# canmotor.net
KiCad netlist of a schematic drawn in EAGLE
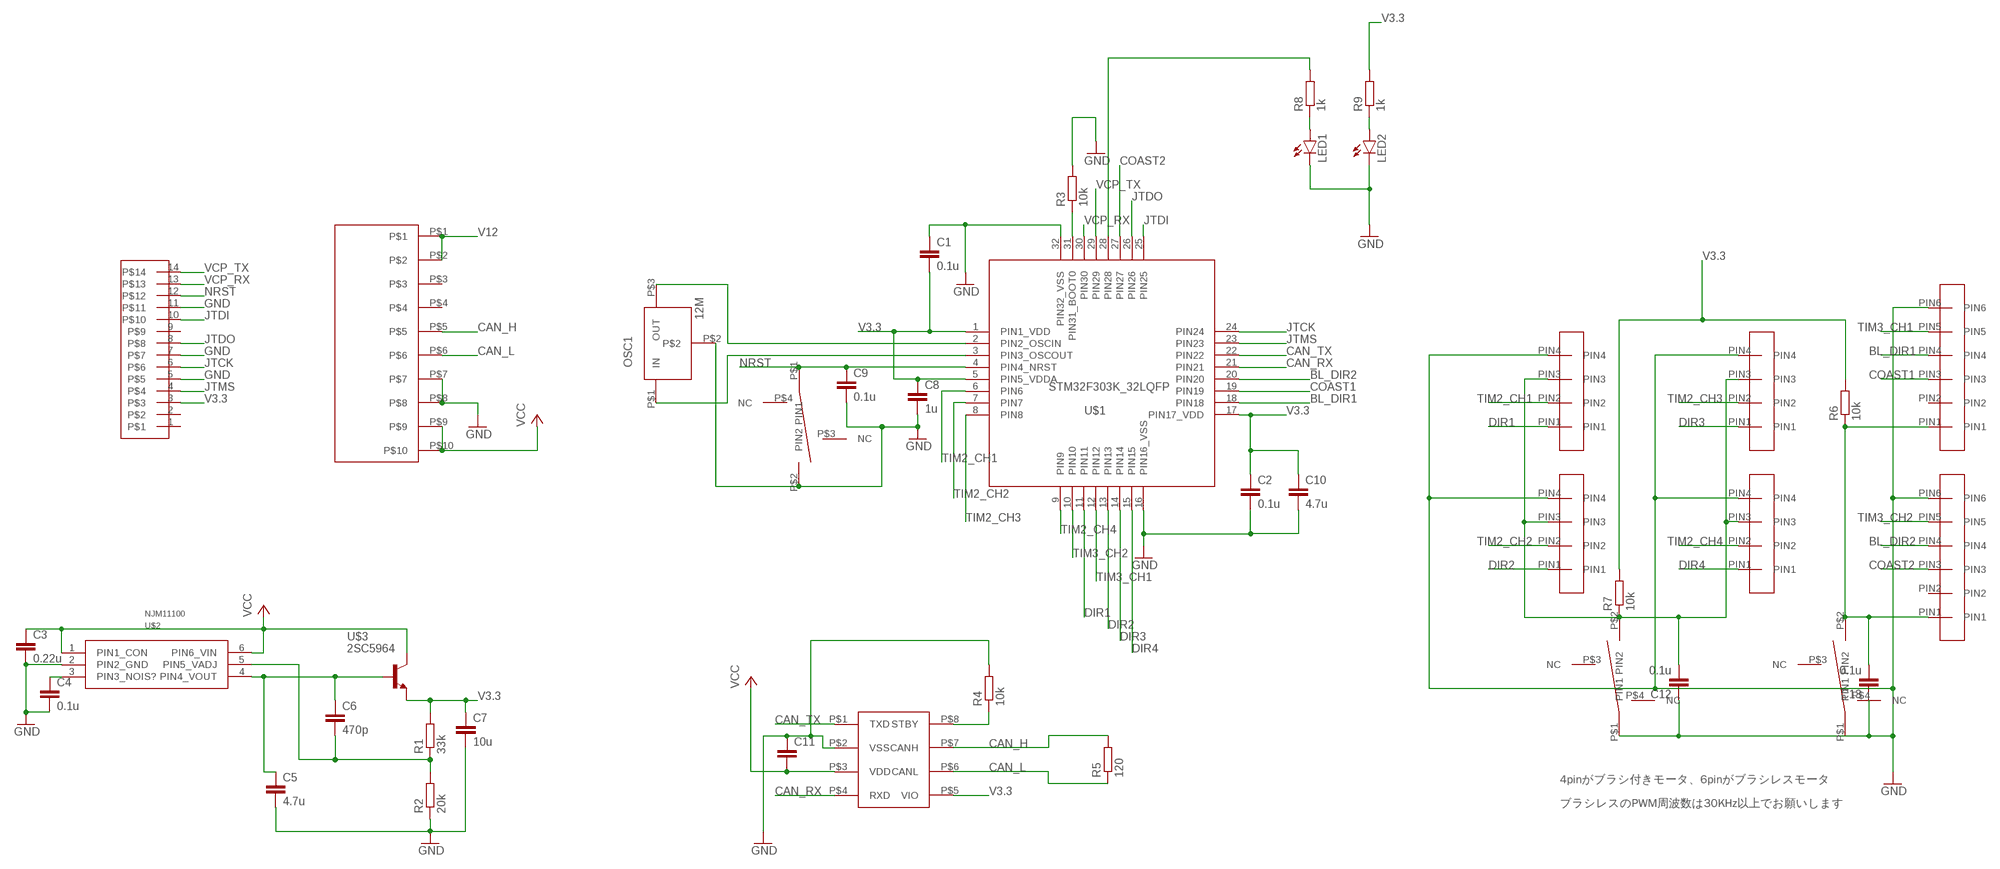
[diagram p0: schematic, sheet 1]

(export (version "E")
  (design (tool "Eeschema 10.0.6"))
  (components
    (comp (ref "BOX10P-L2")
      (value "BOX10PBOX10P-L")
      (footprint "eagle-import:BOX10P-L")
      (libsource (lib "eagle-import") (part "BOX10PBOX10P-L"))
    )
    (comp (ref "C1")
      (value "0.1u")
      (footprint "eagle-import:C1608")
      (libsource (lib "eagle-import") (part "C-EUC1608"))
    )
    (comp (ref "C2")
      (value "0.1u")
      (footprint "eagle-import:C1608")
      (libsource (lib "eagle-import") (part "C-EUC1608"))
    )
    (comp (ref "C3")
      (value "0.22u")
      (footprint "eagle-import:C2012")
      (libsource (lib "eagle-import") (part "C-EUC2012"))
    )
    (comp (ref "C4")
      (value "0.1u")
      (footprint "eagle-import:C1608")
      (libsource (lib "eagle-import") (part "C-EUC1608"))
    )
    (comp (ref "C5")
      (value "4.7u")
      (footprint "eagle-import:C2012")
      (libsource (lib "eagle-import") (part "C-EUC2012"))
    )
    (comp (ref "C6")
      (value "470p")
      (footprint "eagle-import:C1608")
      (libsource (lib "eagle-import") (part "C-EUC1608"))
    )
    (comp (ref "C7")
      (value "10u")
      (footprint "eagle-import:C2012")
      (libsource (lib "eagle-import") (part "C-EUC2012"))
    )
    (comp (ref "C8")
      (value "1u")
      (footprint "eagle-import:C1608")
      (libsource (lib "eagle-import") (part "C-EUC1608"))
    )
    (comp (ref "C9")
      (value "0.1u")
      (footprint "eagle-import:C1608")
      (libsource (lib "eagle-import") (part "C-EUC1608"))
    )
    (comp (ref "C10")
      (value "4.7u")
      (footprint "eagle-import:C2012")
      (libsource (lib "eagle-import") (part "C-EUC2012"))
    )
    (comp (ref "C11")
      (value "C-EUC1608")
      (footprint "eagle-import:C1608")
      (libsource (lib "eagle-import") (part "C-EUC1608"))
    )
    (comp (ref "C12")
      (value "0.1u")
      (footprint "eagle-import:C1608")
      (libsource (lib "eagle-import") (part "C-EUC1608"))
    )
    (comp (ref "C13")
      (value "0.1u")
      (footprint "eagle-import:C1608")
      (libsource (lib "eagle-import") (part "C-EUC1608"))
    )
    (comp (ref "LED1")
      (value "1608LED")
      (footprint "eagle-import:1608")
      (libsource (lib "eagle-import") (part "1608LED"))
    )
    (comp (ref "LED2")
      (value "1608LED")
      (footprint "eagle-import:1608")
      (libsource (lib "eagle-import") (part "1608LED"))
    )
    (comp (ref "OSC1")
      (value "12M")
      (footprint "eagle-import:CSTNE#")
      (libsource (lib "eagle-import") (part "CSTN#"))
    )
    (comp (ref "R1")
      (value "33k")
      (footprint "eagle-import:1608")
      (libsource (lib "eagle-import") (part "R_REG"))
    )
    (comp (ref "R2")
      (value "20k")
      (footprint "eagle-import:1608")
      (libsource (lib "eagle-import") (part "R_REG"))
    )
    (comp (ref "R3")
      (value "10k")
      (footprint "eagle-import:1608")
      (libsource (lib "eagle-import") (part "R_REG"))
    )
    (comp (ref "R4")
      (value "10k")
      (footprint "eagle-import:1608")
      (libsource (lib "eagle-import") (part "R_REG"))
    )
    (comp (ref "R5")
      (value "120")
      (footprint "eagle-import:1608")
      (libsource (lib "eagle-import") (part "R_REG"))
    )
    (comp (ref "R6")
      (value "10k")
      (footprint "eagle-import:1608")
      (libsource (lib "eagle-import") (part "R_REG"))
    )
    (comp (ref "R7")
      (value "10k")
      (footprint "eagle-import:1608")
      (libsource (lib "eagle-import") (part "R_REG"))
    )
    (comp (ref "R8")
      (value "1k")
      (footprint "eagle-import:1608")
      (libsource (lib "eagle-import") (part "R_REG"))
    )
    (comp (ref "R9")
      (value "1k")
      (footprint "eagle-import:1608")
      (libsource (lib "eagle-import") (part "R_REG"))
    )
    (comp (ref "U$1")
      (value "STM32F303K_32LQFP")
      (footprint "eagle-import:LQFP32-7X7")
      (libsource (lib "eagle-import") (part "STM32F303K_32LQFP"))
    )
    (comp (ref "U$2")
      (value "NJM11100")
      (footprint "eagle-import:SOT23-6")
      (libsource (lib "eagle-import") (part "NJM11100"))
    )
    (comp (ref "U$3")
      (value "2SC5964")
      (footprint "eagle-import:PCP")
      (libsource (lib "eagle-import") (part "2SC5964"))
    )
    (comp (ref "U$4")
      (value "TAKUTOSUITTI2")
      (footprint "eagle-import:TAKUTOSUITTI2")
      (libsource (lib "eagle-import") (part "TAKUTOSUITTI2"))
    )
    (comp (ref "U$5")
      (value "MCP2562MCP2561-SN")
      (footprint "eagle-import:SOIC8")
      (libsource (lib "eagle-import") (part "MCP2562MCP2561-SN"))
    )
    (comp (ref "U$6")
      (value "BOX14P")
      (footprint "eagle-import:CON_HEDA14P_1.27")
      (libsource (lib "eagle-import") (part "BOX14P"))
    )
    (comp (ref "U$7")
      (value "DF1B_L_6P")
      (footprint "eagle-import:DF1B_L_6P")
      (libsource (lib "eagle-import") (part "DF1B_L_6P"))
    )
    (comp (ref "U$8")
      (value "DF1B_L_4P")
      (footprint "eagle-import:DF1B_L_4P")
      (libsource (lib "eagle-import") (part "DF1B_L_4P"))
    )
    (comp (ref "U$9")
      (value "DF1B_L_4P")
      (footprint "eagle-import:DF1B_L_4P")
      (libsource (lib "eagle-import") (part "DF1B_L_4P"))
    )
    (comp (ref "U$10")
      (value "DF1B_L_4P")
      (footprint "eagle-import:DF1B_L_4P")
      (libsource (lib "eagle-import") (part "DF1B_L_4P"))
    )
    (comp (ref "U$11")
      (value "DF1B_L_4P")
      (footprint "eagle-import:DF1B_L_4P")
      (libsource (lib "eagle-import") (part "DF1B_L_4P"))
    )
    (comp (ref "U$12")
      (value "DF1B_L_6P")
      (footprint "eagle-import:DF1B_L_6P")
      (libsource (lib "eagle-import") (part "DF1B_L_6P"))
    )
    (comp (ref "U$13")
      (value "TAKUTOSUITTI2")
      (footprint "eagle-import:TAKUTOSUITTI2")
      (libsource (lib "eagle-import") (part "TAKUTOSUITTI2"))
    )
    (comp (ref "U$14")
      (value "TAKUTOSUITTI2")
      (footprint "eagle-import:TAKUTOSUITTI2")
      (libsource (lib "eagle-import") (part "TAKUTOSUITTI2"))
    )
  )
  (nets
    (net (code "1") (name "/BL_DIR1") (class "Default")
      (node (ref "U$1") (pin "18") (pinfunction "PIN18_18") (pintype "bidirectional"))
      (node (ref "U$7") (pin "PIN4") (pinfunction "PIN4_PIN4") (pintype "bidirectional"))
    )
    (net (code "2") (name "/BL_DIR2") (class "Default")
      (node (ref "U$1") (pin "20") (pinfunction "PIN20_20") (pintype "bidirectional"))
      (node (ref "U$12") (pin "PIN4") (pinfunction "PIN4_PIN4") (pintype "bidirectional"))
    )
    (net (code "3") (name "/CAN_H") (class "Default")
      (node (ref "BOX10P-L2") (pin "P$5") (pinfunction "P$5_P$5") (pintype "bidirectional"))
      (node (ref "R5") (pin "2") (pinfunction "2_2") (pintype "passive"))
      (node (ref "U$5") (pin "P$7") (pinfunction "CANH_P$7") (pintype "bidirectional"))
    )
    (net (code "4") (name "/CAN_L") (class "Default")
      (node (ref "BOX10P-L2") (pin "P$6") (pinfunction "P$6_P$6") (pintype "bidirectional"))
      (node (ref "R5") (pin "1") (pinfunction "1_1") (pintype "passive"))
      (node (ref "U$5") (pin "P$6") (pinfunction "CANL_P$6") (pintype "bidirectional"))
    )
    (net (code "5") (name "/CAN_RX") (class "Default")
      (node (ref "U$1") (pin "21") (pinfunction "PIN21_21") (pintype "bidirectional"))
      (node (ref "U$5") (pin "P$4") (pinfunction "RXD_P$4") (pintype "bidirectional"))
    )
    (net (code "6") (name "/CAN_TX") (class "Default")
      (node (ref "U$1") (pin "22") (pinfunction "PIN22_22") (pintype "bidirectional"))
      (node (ref "U$5") (pin "P$1") (pinfunction "TXD_P$1") (pintype "bidirectional"))
    )
    (net (code "7") (name "/COAST1") (class "Default")
      (node (ref "U$1") (pin "19") (pinfunction "PIN19_19") (pintype "bidirectional"))
      (node (ref "U$7") (pin "PIN3") (pinfunction "PIN3_PIN3") (pintype "bidirectional"))
    )
    (net (code "8") (name "/COAST2") (class "Default")
      (node (ref "U$1") (pin "27") (pinfunction "PIN27_27") (pintype "bidirectional"))
      (node (ref "U$12") (pin "PIN3") (pinfunction "PIN3_PIN3") (pintype "bidirectional"))
    )
    (net (code "9") (name "/DIR1") (class "Default")
      (node (ref "U$1") (pin "11") (pinfunction "PIN11_11") (pintype "bidirectional"))
      (node (ref "U$8") (pin "PIN1") (pinfunction "PIN1_PIN1") (pintype "bidirectional"))
    )
    (net (code "10") (name "/DIR2") (class "Default")
      (node (ref "U$1") (pin "13") (pinfunction "PIN13_13") (pintype "bidirectional"))
      (node (ref "U$9") (pin "PIN1") (pinfunction "PIN1_PIN1") (pintype "bidirectional"))
    )
    (net (code "11") (name "/DIR3") (class "Default")
      (node (ref "U$1") (pin "14") (pinfunction "PIN14_14") (pintype "bidirectional"))
      (node (ref "U$10") (pin "PIN1") (pinfunction "PIN1_PIN1") (pintype "bidirectional"))
    )
    (net (code "12") (name "/DIR4") (class "Default")
      (node (ref "U$1") (pin "15") (pinfunction "PIN15_15") (pintype "bidirectional"))
      (node (ref "U$11") (pin "PIN1") (pinfunction "PIN1_PIN1") (pintype "bidirectional"))
    )
    (net (code "13") (name "/JTCK") (class "Default")
      (node (ref "U$1") (pin "24") (pinfunction "PIN24_24") (pintype "bidirectional"))
      (node (ref "U$6") (pin "6") (pinfunction "P$6_6") (pintype "bidirectional"))
    )
    (net (code "14") (name "/JTDI") (class "Default")
      (node (ref "U$1") (pin "25") (pinfunction "PIN25_25") (pintype "bidirectional"))
      (node (ref "U$6") (pin "10") (pinfunction "P$10_10") (pintype "bidirectional"))
    )
    (net (code "15") (name "/JTDO") (class "Default")
      (node (ref "U$1") (pin "26") (pinfunction "PIN26_26") (pintype "bidirectional"))
      (node (ref "U$6") (pin "8") (pinfunction "P$8_8") (pintype "bidirectional"))
    )
    (net (code "16") (name "/JTMS") (class "Default")
      (node (ref "U$1") (pin "23") (pinfunction "PIN23_23") (pintype "bidirectional"))
      (node (ref "U$6") (pin "4") (pinfunction "P$4_4") (pintype "bidirectional"))
    )
    (net (code "17") (name "/NRST") (class "Default")
      (node (ref "C9") (pin "1") (pinfunction "1_1") (pintype "passive"))
      (node (ref "U$1") (pin "4") (pinfunction "PIN4_NRST_4") (pintype "bidirectional"))
      (node (ref "U$4") (pin "P$1") (pinfunction "PIN1_P$1") (pintype "bidirectional"))
      (node (ref "U$6") (pin "12") (pinfunction "P$12_12") (pintype "bidirectional"))
    )
    (net (code "18") (name "/TIM2_CH1") (class "Default")
      (node (ref "U$1") (pin "6") (pinfunction "PIN6_6") (pintype "bidirectional"))
      (node (ref "U$8") (pin "PIN2") (pinfunction "PIN2_PIN2") (pintype "bidirectional"))
    )
    (net (code "19") (name "/TIM2_CH2") (class "Default")
      (node (ref "U$1") (pin "7") (pinfunction "PIN7_7") (pintype "bidirectional"))
      (node (ref "U$9") (pin "PIN2") (pinfunction "PIN2_PIN2") (pintype "bidirectional"))
    )
    (net (code "20") (name "/TIM2_CH3") (class "Default")
      (node (ref "U$1") (pin "8") (pinfunction "PIN8_8") (pintype "bidirectional"))
      (node (ref "U$10") (pin "PIN2") (pinfunction "PIN2_PIN2") (pintype "bidirectional"))
    )
    (net (code "21") (name "/TIM2_CH4") (class "Default")
      (node (ref "U$1") (pin "9") (pinfunction "PIN9_9") (pintype "bidirectional"))
      (node (ref "U$11") (pin "PIN2") (pinfunction "PIN2_PIN2") (pintype "bidirectional"))
    )
    (net (code "22") (name "/TIM3_CH1") (class "Default")
      (node (ref "U$1") (pin "12") (pinfunction "PIN12_12") (pintype "bidirectional"))
      (node (ref "U$7") (pin "PIN5") (pinfunction "PIN5_PIN5") (pintype "bidirectional"))
    )
    (net (code "23") (name "/TIM3_CH2") (class "Default")
      (node (ref "U$1") (pin "10") (pinfunction "PIN10_10") (pintype "bidirectional"))
      (node (ref "U$12") (pin "PIN5") (pinfunction "PIN5_PIN5") (pintype "bidirectional"))
    )
    (net (code "24") (name "/V3.3") (class "Default")
      (node (ref "C1") (pin "2") (pinfunction "2_2") (pintype "passive"))
      (node (ref "C10") (pin "1") (pinfunction "1_1") (pintype "passive"))
      (node (ref "C2") (pin "1") (pinfunction "1_1") (pintype "passive"))
      (node (ref "C7") (pin "1") (pinfunction "1_1") (pintype "passive"))
      (node (ref "C8") (pin "1") (pinfunction "1_1") (pintype "passive"))
      (node (ref "R1") (pin "2") (pinfunction "2_2") (pintype "passive"))
      (node (ref "R6") (pin "2") (pinfunction "2_2") (pintype "passive"))
      (node (ref "R7") (pin "2") (pinfunction "2_2") (pintype "passive"))
      (node (ref "R9") (pin "2") (pinfunction "2_2") (pintype "passive"))
      (node (ref "U$1") (pin "1") (pinfunction "PIN1_VDD_1") (pintype "bidirectional"))
      (node (ref "U$1") (pin "17") (pinfunction "PIN17_VDD_17") (pintype "bidirectional"))
      (node (ref "U$1") (pin "5") (pinfunction "PIN5_VDDA_5") (pintype "bidirectional"))
      (node (ref "U$3") (pin "3") (pinfunction "E_3") (pintype "passive"))
      (node (ref "U$5") (pin "P$5") (pinfunction "VIO_P$5") (pintype "bidirectional"))
      (node (ref "U$6") (pin "3") (pinfunction "P$3_3") (pintype "bidirectional"))
    )
    (net (code "25") (name "/V12") (class "Default")
      (node (ref "BOX10P-L2") (pin "P$1") (pinfunction "P$1_P$1") (pintype "bidirectional"))
      (node (ref "BOX10P-L2") (pin "P$2") (pinfunction "P$2_P$2") (pintype "bidirectional"))
    )
    (net (code "26") (name "/VCP_RX") (class "Default")
      (node (ref "U$1") (pin "30") (pinfunction "PIN30_30") (pintype "bidirectional"))
      (node (ref "U$6") (pin "13") (pinfunction "P$13_13") (pintype "bidirectional"))
    )
    (net (code "27") (name "/VCP_TX") (class "Default")
      (node (ref "U$1") (pin "29") (pinfunction "PIN29_29") (pintype "bidirectional"))
      (node (ref "U$6") (pin "14") (pinfunction "P$14_14") (pintype "bidirectional"))
    )
    (net (code "28") (name "GND") (class "Default")
      (node (ref "BOX10P-L2") (pin "P$7") (pinfunction "P$7_P$7") (pintype "bidirectional"))
      (node (ref "BOX10P-L2") (pin "P$8") (pinfunction "P$8_P$8") (pintype "bidirectional"))
      (node (ref "C1") (pin "1") (pinfunction "1_1") (pintype "passive"))
      (node (ref "C10") (pin "2") (pinfunction "2_2") (pintype "passive"))
      (node (ref "C11") (pin "1") (pinfunction "1_1") (pintype "passive"))
      (node (ref "C12") (pin "1") (pinfunction "1_1") (pintype "passive"))
      (node (ref "C13") (pin "1") (pinfunction "1_1") (pintype "passive"))
      (node (ref "C2") (pin "2") (pinfunction "2_2") (pintype "passive"))
      (node (ref "C3") (pin "2") (pinfunction "2_2") (pintype "passive"))
      (node (ref "C4") (pin "2") (pinfunction "2_2") (pintype "passive"))
      (node (ref "C5") (pin "2") (pinfunction "2_2") (pintype "passive"))
      (node (ref "C7") (pin "2") (pinfunction "2_2") (pintype "passive"))
      (node (ref "C8") (pin "2") (pinfunction "2_2") (pintype "passive"))
      (node (ref "C9") (pin "2") (pinfunction "2_2") (pintype "passive"))
      (node (ref "LED1") (pin "K") (pinfunction "K_K") (pintype "passive"))
      (node (ref "LED2") (pin "K") (pinfunction "K_K") (pintype "passive"))
      (node (ref "OSC1") (pin "P$2") (pinfunction "P$2_P$2") (pintype "bidirectional"))
      (node (ref "R2") (pin "1") (pinfunction "1_1") (pintype "passive"))
      (node (ref "R3") (pin "2") (pinfunction "2_2") (pintype "passive"))
      (node (ref "R4") (pin "2") (pinfunction "2_2") (pintype "passive"))
      (node (ref "U$1") (pin "16") (pinfunction "PIN16_VSS_16") (pintype "bidirectional"))
      (node (ref "U$1") (pin "32") (pinfunction "PIN32_VSS_32") (pintype "bidirectional"))
      (node (ref "U$10") (pin "PIN4") (pinfunction "PIN4_PIN4") (pintype "bidirectional"))
      (node (ref "U$11") (pin "PIN4") (pinfunction "PIN4_PIN4") (pintype "bidirectional"))
      (node (ref "U$12") (pin "PIN6") (pinfunction "PIN6_PIN6") (pintype "bidirectional"))
      (node (ref "U$13") (pin "P$1") (pinfunction "PIN1_P$1") (pintype "bidirectional"))
      (node (ref "U$14") (pin "P$1") (pinfunction "PIN1_P$1") (pintype "bidirectional"))
      (node (ref "U$2") (pin "2") (pinfunction "PIN2_GND_2") (pintype "bidirectional"))
      (node (ref "U$4") (pin "P$2") (pinfunction "PIN2_P$2") (pintype "bidirectional"))
      (node (ref "U$5") (pin "P$2") (pinfunction "VSS_P$2") (pintype "bidirectional"))
      (node (ref "U$6") (pin "11") (pinfunction "P$11_11") (pintype "bidirectional"))
      (node (ref "U$6") (pin "5") (pinfunction "P$5_5") (pintype "bidirectional"))
      (node (ref "U$6") (pin "7") (pinfunction "P$7_7") (pintype "bidirectional"))
      (node (ref "U$7") (pin "PIN6") (pinfunction "PIN6_PIN6") (pintype "bidirectional"))
      (node (ref "U$8") (pin "PIN4") (pinfunction "PIN4_PIN4") (pintype "bidirectional"))
      (node (ref "U$9") (pin "PIN4") (pinfunction "PIN4_PIN4") (pintype "bidirectional"))
    )
    (net (code "29") (name "Net-(LED1-PadA)") (class "Default")
      (node (ref "LED1") (pin "A") (pinfunction "A_A") (pintype "passive"))
      (node (ref "R8") (pin "1") (pinfunction "1_1") (pintype "passive"))
    )
    (net (code "30") (name "Net-(LED2-PadA)") (class "Default")
      (node (ref "LED2") (pin "A") (pinfunction "A_A") (pintype "passive"))
      (node (ref "R9") (pin "1") (pinfunction "1_1") (pintype "passive"))
    )
    (net (code "31") (name "Net-(OSC1-IN)") (class "Default")
      (node (ref "OSC1") (pin "P$1") (pinfunction "IN_P$1") (pintype "bidirectional"))
      (node (ref "U$1") (pin "3") (pinfunction "PIN3_OSCOUT_3") (pintype "bidirectional"))
    )
    (net (code "32") (name "Net-(OSC1-OUT)") (class "Default")
      (node (ref "OSC1") (pin "P$3") (pinfunction "OUT_P$3") (pintype "bidirectional"))
      (node (ref "U$1") (pin "2") (pinfunction "PIN2_OSCIN_2") (pintype "bidirectional"))
    )
    (net (code "33") (name "Net-(U$1-PIN28)") (class "Default")
      (node (ref "R8") (pin "2") (pinfunction "2_2") (pintype "passive"))
      (node (ref "U$1") (pin "28") (pinfunction "PIN28_28") (pintype "bidirectional"))
    )
    (net (code "34") (name "Net-(U$1-PIN31_BOOT0)") (class "Default")
      (node (ref "R3") (pin "1") (pinfunction "1_1") (pintype "passive"))
      (node (ref "U$1") (pin "31") (pinfunction "PIN31_BOOT0_31") (pintype "bidirectional"))
    )
    (net (code "35") (name "Net-(U$2-PIN3_NOIS?)") (class "Default")
      (node (ref "C4") (pin "1") (pinfunction "1_1") (pintype "passive"))
      (node (ref "U$2") (pin "3") (pinfunction "PIN3_NOIS?_3") (pintype "bidirectional"))
    )
    (net (code "36") (name "Net-(U$2-PIN4_VOUT)") (class "Default")
      (node (ref "C5") (pin "1") (pinfunction "1_1") (pintype "passive"))
      (node (ref "C6") (pin "1") (pinfunction "1_1") (pintype "passive"))
      (node (ref "U$2") (pin "4") (pinfunction "PIN4_VOUT_4") (pintype "bidirectional"))
      (node (ref "U$3") (pin "1") (pinfunction "B_1") (pintype "passive"))
    )
    (net (code "37") (name "Net-(U$2-PIN5_VADJ)") (class "Default")
      (node (ref "C6") (pin "2") (pinfunction "2_2") (pintype "passive"))
      (node (ref "R1") (pin "1") (pinfunction "1_1") (pintype "passive"))
      (node (ref "R2") (pin "2") (pinfunction "2_2") (pintype "passive"))
      (node (ref "U$2") (pin "5") (pinfunction "PIN5_VADJ_5") (pintype "bidirectional"))
    )
    (net (code "38") (name "Net-(U$5-STBY)") (class "Default")
      (node (ref "R4") (pin "1") (pinfunction "1_1") (pintype "passive"))
      (node (ref "U$5") (pin "P$8") (pinfunction "STBY_P$8") (pintype "bidirectional"))
    )
    (net (code "39") (name "Net-(U$13-PIN2)") (class "Default")
      (node (ref "C13") (pin "2") (pinfunction "2_2") (pintype "passive"))
      (node (ref "R6") (pin "1") (pinfunction "1_1") (pintype "passive"))
      (node (ref "U$12") (pin "PIN1") (pinfunction "PIN1_PIN1") (pintype "bidirectional"))
      (node (ref "U$13") (pin "P$2") (pinfunction "PIN2_P$2") (pintype "bidirectional"))
      (node (ref "U$7") (pin "PIN1") (pinfunction "PIN1_PIN1") (pintype "bidirectional"))
    )
    (net (code "40") (name "Net-(U$14-PIN2)") (class "Default")
      (node (ref "C12") (pin "2") (pinfunction "2_2") (pintype "passive"))
      (node (ref "R7") (pin "1") (pinfunction "1_1") (pintype "passive"))
      (node (ref "U$10") (pin "PIN3") (pinfunction "PIN3_PIN3") (pintype "bidirectional"))
      (node (ref "U$11") (pin "PIN3") (pinfunction "PIN3_PIN3") (pintype "bidirectional"))
      (node (ref "U$14") (pin "P$2") (pinfunction "PIN2_P$2") (pintype "bidirectional"))
      (node (ref "U$8") (pin "PIN3") (pinfunction "PIN3_PIN3") (pintype "bidirectional"))
      (node (ref "U$9") (pin "PIN3") (pinfunction "PIN3_PIN3") (pintype "bidirectional"))
    )
    (net (code "41") (name "VCC") (class "Default")
      (node (ref "BOX10P-L2") (pin "P$10") (pinfunction "P$10_P$10") (pintype "bidirectional"))
      (node (ref "BOX10P-L2") (pin "P$9") (pinfunction "P$9_P$9") (pintype "bidirectional"))
      (node (ref "C11") (pin "2") (pinfunction "2_2") (pintype "passive"))
      (node (ref "C3") (pin "1") (pinfunction "1_1") (pintype "passive"))
      (node (ref "U$2") (pin "1") (pinfunction "PIN1_CON_1") (pintype "bidirectional"))
      (node (ref "U$2") (pin "6") (pinfunction "PIN6_VIN_6") (pintype "bidirectional"))
      (node (ref "U$3") (pin "2") (pinfunction "C_2") (pintype "passive"))
      (node (ref "U$3") (pin "2@2") (pinfunction "C_2@2") (pintype "passive"))
      (node (ref "U$5") (pin "P$3") (pinfunction "VDD_P$3") (pintype "bidirectional"))
    )
    (net (code "42") (name "unconnected-(BOX10P-L2-PadP$3)") (class "Default")
      (node (ref "BOX10P-L2") (pin "P$3") (pinfunction "P$3_P$3") (pintype "bidirectional"))
    )
    (net (code "43") (name "unconnected-(BOX10P-L2-PadP$4)") (class "Default")
      (node (ref "BOX10P-L2") (pin "P$4") (pinfunction "P$4_P$4") (pintype "bidirectional"))
    )
    (net (code "44") (name "unconnected-(U$4-NC-PadP$3)") (class "Default")
      (node (ref "U$4") (pin "P$3") (pinfunction "NC_P$3") (pintype "bidirectional"))
    )
    (net (code "45") (name "unconnected-(U$4-NC-PadP$4)") (class "Default")
      (node (ref "U$4") (pin "P$4") (pinfunction "NC_P$4") (pintype "bidirectional"))
    )
    (net (code "46") (name "unconnected-(U$6-P$1-Pad1)") (class "Default")
      (node (ref "U$6") (pin "1") (pinfunction "P$1_1") (pintype "bidirectional"))
    )
    (net (code "47") (name "unconnected-(U$6-P$2-Pad2)") (class "Default")
      (node (ref "U$6") (pin "2") (pinfunction "P$2_2") (pintype "bidirectional"))
    )
    (net (code "48") (name "unconnected-(U$6-P$9-Pad9)") (class "Default")
      (node (ref "U$6") (pin "9") (pinfunction "P$9_9") (pintype "bidirectional"))
    )
    (net (code "49") (name "unconnected-(U$7-PadPIN2)") (class "Default")
      (node (ref "U$7") (pin "PIN2") (pinfunction "PIN2_PIN2") (pintype "bidirectional"))
    )
    (net (code "50") (name "unconnected-(U$12-PadPIN2)") (class "Default")
      (node (ref "U$12") (pin "PIN2") (pinfunction "PIN2_PIN2") (pintype "bidirectional"))
    )
    (net (code "51") (name "unconnected-(U$13-NC-PadP$3)") (class "Default")
      (node (ref "U$13") (pin "P$3") (pinfunction "NC_P$3") (pintype "bidirectional"))
    )
    (net (code "52") (name "unconnected-(U$13-NC-PadP$4)") (class "Default")
      (node (ref "U$13") (pin "P$4") (pinfunction "NC_P$4") (pintype "bidirectional"))
    )
    (net (code "53") (name "unconnected-(U$14-NC-PadP$3)") (class "Default")
      (node (ref "U$14") (pin "P$3") (pinfunction "NC_P$3") (pintype "bidirectional"))
    )
    (net (code "54") (name "unconnected-(U$14-NC-PadP$4)") (class "Default")
      (node (ref "U$14") (pin "P$4") (pinfunction "NC_P$4") (pintype "bidirectional"))
    )
  )
)
